# ESP12_Breakout.net
KiCad netlist of a schematic drawn in EAGLE
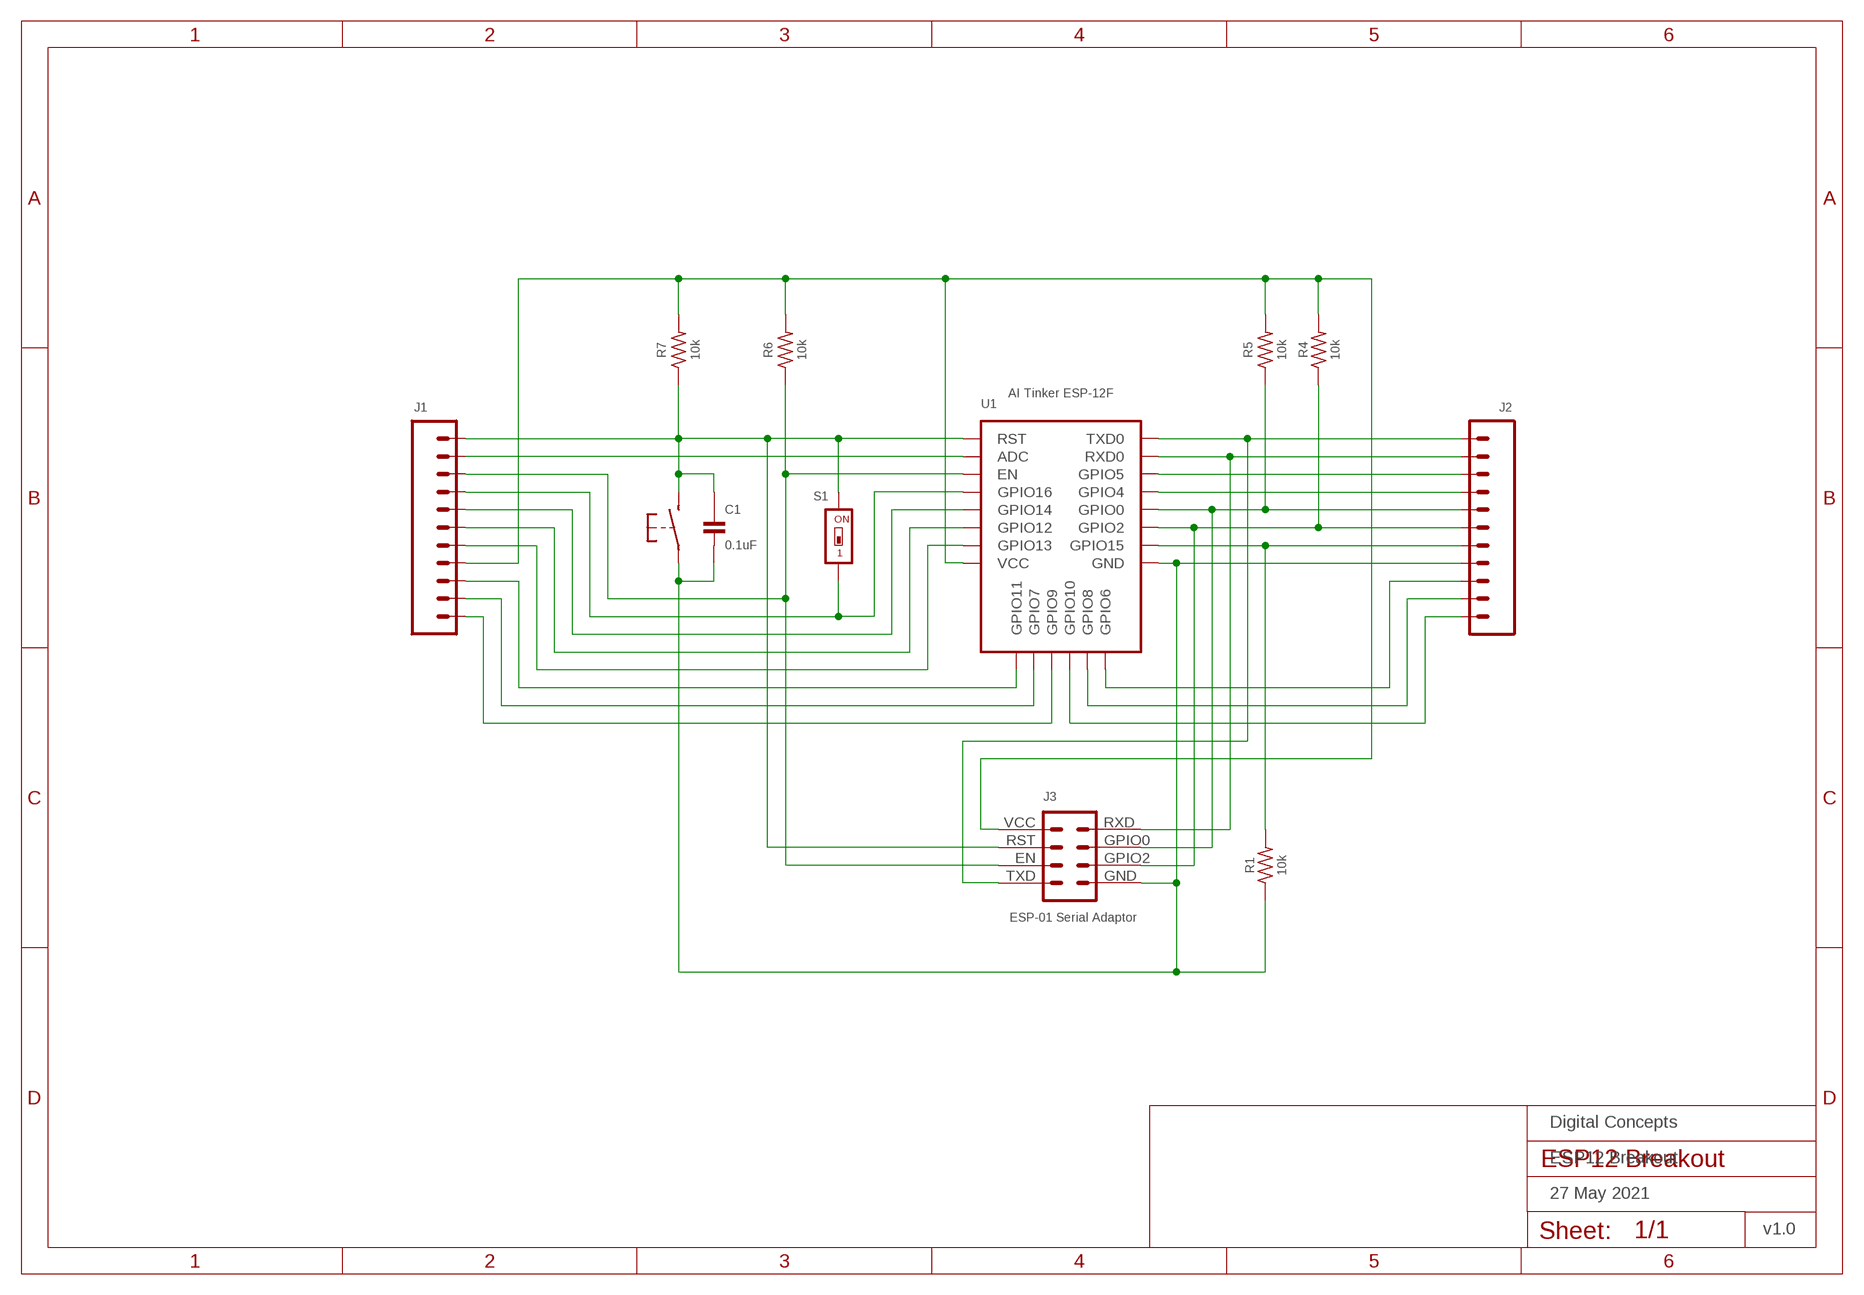
[diagram p0: schematic, sheet 1]

(export (version "E")
  (design (tool "Eeschema 10.0.6"))
  (components
    (comp (ref "C1")
      (value "0.1uF")
      (footprint "eagle-import:C0805")
      (libsource (lib "eagle-import") (part "CAPACITOR-0805"))
    )
    (comp (ref "J1")
      (value "HEADER-1X11-GENERIC")
      (footprint "eagle-import:CONN_11-GENERIC")
      (libsource (lib "eagle-import") (part "HEADER-1X11-GENERIC"))
    )
    (comp (ref "J2")
      (value "HEADER-1X11-GENERIC")
      (footprint "eagle-import:CONN_11-GENERIC")
      (libsource (lib "eagle-import") (part "HEADER-1X11-GENERIC"))
    )
    (comp (ref "J3")
      (value "ESP-01 Serial Adaptor")
      (footprint "eagle-import:CONN_2X4-ESP-01-SERIAL")
      (libsource (lib "eagle-import") (part "ESP-01-SERIAL-ADAPTOR"))
    )
    (comp (ref "R1")
      (value "10k")
      (footprint "eagle-import:R0805-VIA-2")
      (libsource (lib "eagle-import") (part "RESISTOR-VIA-2"))
    )
    (comp (ref "R4")
      (value "10k")
      (footprint "eagle-import:R0805-VIA-2")
      (libsource (lib "eagle-import") (part "RESISTOR-VIA-2"))
    )
    (comp (ref "R5")
      (value "10k")
      (footprint "eagle-import:R0805")
      (libsource (lib "eagle-import") (part "RESISTORR0805"))
    )
    (comp (ref "R6")
      (value "10k")
      (footprint "eagle-import:R0805")
      (libsource (lib "eagle-import") (part "RESISTORR0805"))
    )
    (comp (ref "R7")
      (value "10k")
      (footprint "eagle-import:R0805")
      (libsource (lib "eagle-import") (part "RESISTORR0805"))
    )
    (comp (ref "S1")
      (value "Wake")
      (footprint "eagle-import:SMD-001")
      (libsource (lib "eagle-import") (part "SWITCH-DIP-SWS001"))
    )
    (comp (ref "S2")
      (value "SWITCH-MOMENTARY-2-PIN")
      (footprint "eagle-import:SWITCH-2-PAD")
      (libsource (lib "eagle-import") (part "SWITCH-MOMENTARY-2-PIN"))
    )
    (comp (ref "U1")
      (value "AI Tinker ESP-12F")
      (footprint "eagle-import:ESP-12E_F")
      (libsource (lib "eagle-import") (part "ESP-12E/F"))
    )
  )
  (nets
    (net (code "1") (name "Net-(J1-Pad1)") (class "Default")
      (node (ref "J1") (pin "1") (pinfunction "1_1") (pintype "passive"))
      (node (ref "U1") (pin "GPIO9") (pinfunction "GPIO9_GPIO9") (pintype "bidirectional"))
    )
    (net (code "2") (name "Net-(J1-Pad5)") (class "Default")
      (node (ref "J1") (pin "5") (pinfunction "5_5") (pintype "passive"))
      (node (ref "U1") (pin "GPIO13") (pinfunction "GPIO13_GPIO13") (pintype "bidirectional"))
    )
    (net (code "3") (name "Net-(J1-Pad6)") (class "Default")
      (node (ref "J1") (pin "6") (pinfunction "6_6") (pintype "passive"))
      (node (ref "U1") (pin "GPIO12") (pinfunction "GPIO12_GPIO12") (pintype "bidirectional"))
    )
    (net (code "4") (name "Net-(J1-Pad7)") (class "Default")
      (node (ref "J1") (pin "7") (pinfunction "7_7") (pintype "passive"))
      (node (ref "U1") (pin "GPIO14") (pinfunction "GPIO14_GPIO14") (pintype "bidirectional"))
    )
    (net (code "5") (name "Net-(J1-Pad8)") (class "Default")
      (node (ref "J1") (pin "8") (pinfunction "8_8") (pintype "passive"))
      (node (ref "S1") (pin "1") (pinfunction "1_1") (pintype "passive"))
      (node (ref "U1") (pin "GPIO16") (pinfunction "GPIO16_GPIO16") (pintype "bidirectional"))
    )
    (net (code "6") (name "Net-(J1-Pad10)") (class "Default")
      (node (ref "J1") (pin "10") (pinfunction "10_10") (pintype "passive"))
      (node (ref "U1") (pin "ADC") (pinfunction "ADC_ADC") (pintype "bidirectional"))
    )
    (net (code "7") (name "Net-(J2-Pad1)") (class "Default")
      (node (ref "J2") (pin "1") (pinfunction "1_1") (pintype "passive"))
      (node (ref "U1") (pin "GPIO10") (pinfunction "GPIO10_GPIO10") (pintype "bidirectional"))
    )
    (net (code "8") (name "Net-(J2-Pad5)") (class "Default")
      (node (ref "J2") (pin "5") (pinfunction "5_5") (pintype "passive"))
      (node (ref "R1") (pin "2") (pinfunction "2_2") (pintype "passive"))
      (node (ref "R1") (pin "2@VIA") (pinfunction "2_2@VIA") (pintype "passive"))
      (node (ref "U1") (pin "GPIO15") (pinfunction "GPIO15_GPIO15") (pintype "bidirectional"))
    )
    (net (code "9") (name "Net-(J2-Pad8)") (class "Default")
      (node (ref "J2") (pin "8") (pinfunction "8_8") (pintype "passive"))
      (node (ref "U1") (pin "GPIO4") (pinfunction "GPIO4_GPIO4") (pintype "bidirectional"))
    )
    (net (code "10") (name "Net-(J2-Pad9)") (class "Default")
      (node (ref "J2") (pin "9") (pinfunction "9_9") (pintype "passive"))
      (node (ref "U1") (pin "GPIO5") (pinfunction "GPIO5_GPIO5") (pintype "bidirectional"))
    )
    (net (code "11") (name "Net-(J3-1)") (class "Default")
      (node (ref "C1") (pin "2") (pinfunction "2_2") (pintype "passive"))
      (node (ref "J2") (pin "4") (pinfunction "4_4") (pintype "passive"))
      (node (ref "J3") (pin "GND") (pinfunction "1_GND") (pintype "passive"))
      (node (ref "R1") (pin "1") (pinfunction "1_1") (pintype "passive"))
      (node (ref "S2") (pin "P$1") (pinfunction "P_P$1") (pintype "passive"))
      (node (ref "U1") (pin "GND") (pinfunction "GND_GND") (pintype "bidirectional"))
    )
    (net (code "12") (name "Net-(J3-2)") (class "Default")
      (node (ref "J2") (pin "6") (pinfunction "6_6") (pintype "passive"))
      (node (ref "J3") (pin "GPIO2") (pinfunction "2_GPIO2") (pintype "passive"))
      (node (ref "R4") (pin "1") (pinfunction "1_1") (pintype "passive"))
      (node (ref "U1") (pin "GPIO2") (pinfunction "GPIO2_GPIO2") (pintype "bidirectional"))
    )
    (net (code "13") (name "Net-(J3-3)") (class "Default")
      (node (ref "J2") (pin "7") (pinfunction "7_7") (pintype "passive"))
      (node (ref "J3") (pin "GPIO0") (pinfunction "3_GPIO0") (pintype "passive"))
      (node (ref "R5") (pin "1") (pinfunction "1_1") (pintype "passive"))
      (node (ref "U1") (pin "GPIO0") (pinfunction "GPIO0_GPIO0") (pintype "bidirectional"))
    )
    (net (code "14") (name "Net-(J3-4)") (class "Default")
      (node (ref "J2") (pin "10") (pinfunction "10_10") (pintype "passive"))
      (node (ref "J3") (pin "RXD") (pinfunction "4_RXD") (pintype "passive"))
      (node (ref "U1") (pin "RXD0") (pinfunction "RXD0_RXD0") (pintype "bidirectional"))
    )
    (net (code "15") (name "Net-(J3-5)") (class "Default")
      (node (ref "J1") (pin "4") (pinfunction "4_4") (pintype "passive"))
      (node (ref "J3") (pin "VCC") (pinfunction "5_VCC") (pintype "passive"))
      (node (ref "R4") (pin "2") (pinfunction "2_2") (pintype "passive"))
      (node (ref "R4") (pin "2@VIA") (pinfunction "2_2@VIA") (pintype "passive"))
      (node (ref "R5") (pin "2") (pinfunction "2_2") (pintype "passive"))
      (node (ref "R6") (pin "2") (pinfunction "2_2") (pintype "passive"))
      (node (ref "R7") (pin "2") (pinfunction "2_2") (pintype "passive"))
      (node (ref "U1") (pin "VCC") (pinfunction "VCC_VCC") (pintype "bidirectional"))
    )
    (net (code "16") (name "Net-(J3-6)") (class "Default")
      (node (ref "C1") (pin "1") (pinfunction "1_1") (pintype "passive"))
      (node (ref "J1") (pin "11") (pinfunction "11_11") (pintype "passive"))
      (node (ref "J3") (pin "RST") (pinfunction "6_RST") (pintype "passive"))
      (node (ref "R7") (pin "1") (pinfunction "1_1") (pintype "passive"))
      (node (ref "S1") (pin "2") (pinfunction "2_2") (pintype "passive"))
      (node (ref "S2") (pin "P$2") (pinfunction "S_P$2") (pintype "passive"))
      (node (ref "U1") (pin "RST") (pinfunction "RST_RST") (pintype "bidirectional"))
    )
    (net (code "17") (name "Net-(J3-7)") (class "Default")
      (node (ref "J1") (pin "9") (pinfunction "9_9") (pintype "passive"))
      (node (ref "J3") (pin "EN") (pinfunction "7_EN") (pintype "passive"))
      (node (ref "R6") (pin "1") (pinfunction "1_1") (pintype "passive"))
      (node (ref "U1") (pin "EN") (pinfunction "EN_EN") (pintype "bidirectional"))
    )
    (net (code "18") (name "Net-(J3-8)") (class "Default")
      (node (ref "J2") (pin "11") (pinfunction "11_11") (pintype "passive"))
      (node (ref "J3") (pin "TXD") (pinfunction "8_TXD") (pintype "passive"))
      (node (ref "U1") (pin "TXD0") (pinfunction "TXD0_TXD0") (pintype "bidirectional"))
    )
    (net (code "19") (name "Net-(U1-GPIO6)") (class "Default")
      (node (ref "J2") (pin "3") (pinfunction "3_3") (pintype "passive"))
      (node (ref "U1") (pin "SCLK") (pinfunction "GPIO6_SCLK") (pintype "bidirectional"))
    )
    (net (code "20") (name "Net-(U1-GPIO7)") (class "Default")
      (node (ref "J1") (pin "2") (pinfunction "2_2") (pintype "passive"))
      (node (ref "U1") (pin "MISO") (pinfunction "GPIO7_MISO") (pintype "bidirectional"))
    )
    (net (code "21") (name "Net-(U1-GPIO8)") (class "Default")
      (node (ref "J2") (pin "2") (pinfunction "2_2") (pintype "passive"))
      (node (ref "U1") (pin "MOSI") (pinfunction "GPIO8_MOSI") (pintype "bidirectional"))
    )
    (net (code "22") (name "Net-(U1-GPIO11)") (class "Default")
      (node (ref "J1") (pin "3") (pinfunction "3_3") (pintype "passive"))
      (node (ref "U1") (pin "CS0") (pinfunction "GPIO11_CS0") (pintype "bidirectional"))
    )
  )
)
